# GCtoUSBv1_2.net
KiCad netlist of a schematic drawn in EAGLE
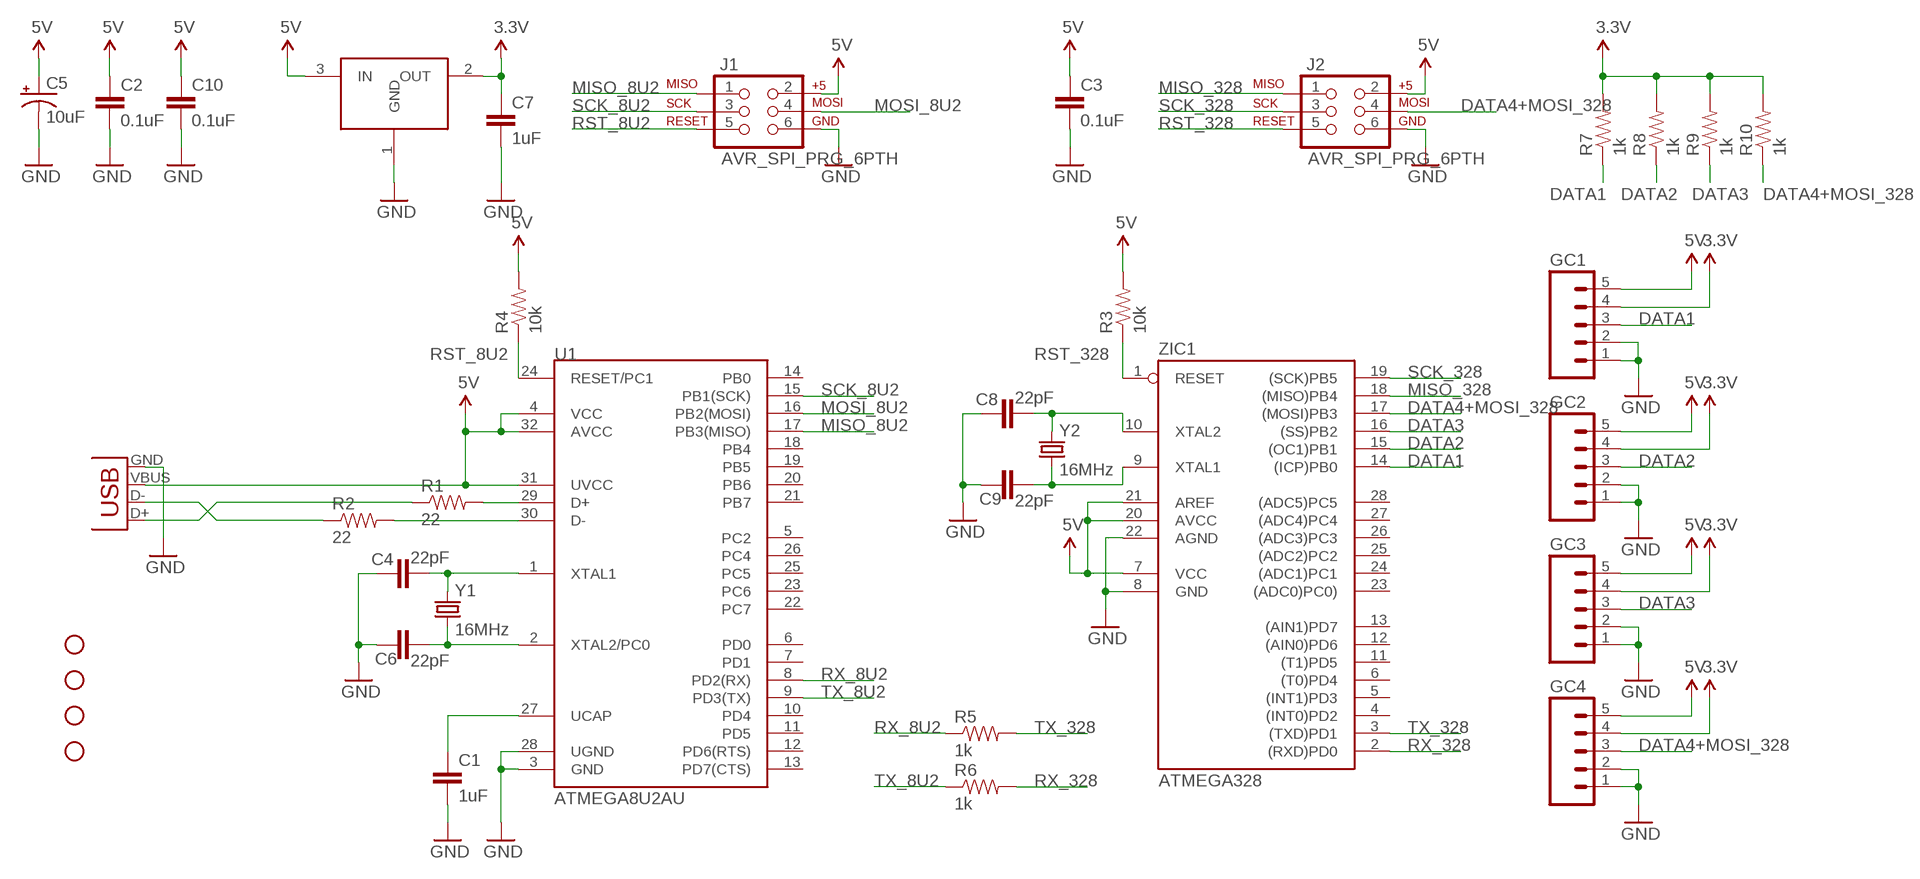
[diagram p0: schematic, sheet 1]

(export (version "E")
  (design (tool "Eeschema 10.0.6"))
  (components
    (comp (ref "C1")
      (value "1uF")
      (footprint "eagle-import:CAP-PTH-5MM")
      (libsource (lib "eagle-import") (part "CAPPTH1"))
    )
    (comp (ref "C2")
      (value "0.1uF")
      (footprint "eagle-import:CAP-PTH-SMALL")
      (libsource (lib "eagle-import") (part "CAPPTH"))
    )
    (comp (ref "C3")
      (value "0.1uF")
      (footprint "eagle-import:CAP-PTH-SMALL")
      (libsource (lib "eagle-import") (part "CAPPTH"))
    )
    (comp (ref "C4")
      (value "22pF")
      (footprint "eagle-import:CAP-PTH-SMALL")
      (libsource (lib "eagle-import") (part "CAPPTH"))
    )
    (comp (ref "C5")
      (value "10uF")
      (footprint "eagle-import:CPOL-RADIAL-10UF-25V")
      (libsource (lib "eagle-import") (part "CAP_POLPTH2"))
    )
    (comp (ref "C6")
      (value "22pF")
      (footprint "eagle-import:CAP-PTH-SMALL")
      (libsource (lib "eagle-import") (part "CAPPTH"))
    )
    (comp (ref "C7")
      (value "1uF")
      (footprint "eagle-import:CAP-PTH-5MM")
      (libsource (lib "eagle-import") (part "CAPPTH1"))
    )
    (comp (ref "C8")
      (value "22pF")
      (footprint "eagle-import:CAP-PTH-SMALL")
      (libsource (lib "eagle-import") (part "CAPPTH"))
    )
    (comp (ref "C9")
      (value "22pF")
      (footprint "eagle-import:CAP-PTH-SMALL")
      (libsource (lib "eagle-import") (part "CAPPTH"))
    )
    (comp (ref "C10")
      (value "0.1uF")
      (footprint "eagle-import:CAP-PTH-SMALL")
      (libsource (lib "eagle-import") (part "CAPPTH"))
    )
    (comp (ref "GC1")
      (value "M05PTH")
      (footprint "eagle-import:1X05")
      (libsource (lib "eagle-import") (part "M05PTH"))
    )
    (comp (ref "GC2")
      (value "M05PTH")
      (footprint "eagle-import:1X05")
      (libsource (lib "eagle-import") (part "M05PTH"))
    )
    (comp (ref "GC3")
      (value "M05PTH")
      (footprint "eagle-import:1X05")
      (libsource (lib "eagle-import") (part "M05PTH"))
    )
    (comp (ref "GC4")
      (value "M05PTH")
      (footprint "eagle-import:1X05")
      (libsource (lib "eagle-import") (part "M05PTH"))
    )
    (comp (ref "J1")
      (value "AVR_SPI_PRG_6PTH")
      (footprint "eagle-import:2X3")
      (libsource (lib "eagle-import") (part "AVR_SPI_PRG_6PTH"))
    )
    (comp (ref "J2")
      (value "AVR_SPI_PRG_6PTH")
      (footprint "eagle-import:2X3")
      (libsource (lib "eagle-import") (part "AVR_SPI_PRG_6PTH"))
    )
    (comp (ref "JP5")
      (value "STAND-OFF")
      (footprint "eagle-import:STAND-OFF")
      (libsource (lib "eagle-import") (part "STAND-OFF"))
    )
    (comp (ref "JP6")
      (value "STAND-OFF")
      (footprint "eagle-import:STAND-OFF")
      (libsource (lib "eagle-import") (part "STAND-OFF"))
    )
    (comp (ref "JP7")
      (value "STAND-OFF")
      (footprint "eagle-import:STAND-OFF")
      (libsource (lib "eagle-import") (part "STAND-OFF"))
    )
    (comp (ref "JP8")
      (value "STAND-OFF")
      (footprint "eagle-import:STAND-OFF")
      (libsource (lib "eagle-import") (part "STAND-OFF"))
    )
    (comp (ref "R1")
      (value "22")
      (footprint "eagle-import:AXIAL-0.4")
      (libsource (lib "eagle-import") (part "RESISTORPTH-1/4W"))
    )
    (comp (ref "R2")
      (value "22")
      (footprint "eagle-import:AXIAL-0.4")
      (libsource (lib "eagle-import") (part "RESISTORPTH-1/4W"))
    )
    (comp (ref "R3")
      (value "10k")
      (footprint "eagle-import:AXIAL-0.4")
      (libsource (lib "eagle-import") (part "RESISTORPTH-1/4W"))
    )
    (comp (ref "R4")
      (value "10k")
      (footprint "eagle-import:AXIAL-0.4")
      (libsource (lib "eagle-import") (part "RESISTORPTH-1/4W"))
    )
    (comp (ref "R5")
      (value "1k")
      (footprint "eagle-import:AXIAL-0.4")
      (libsource (lib "eagle-import") (part "RESISTORPTH-1/4W"))
    )
    (comp (ref "R6")
      (value "1k")
      (footprint "eagle-import:AXIAL-0.4")
      (libsource (lib "eagle-import") (part "RESISTORPTH-1/4W"))
    )
    (comp (ref "R7")
      (value "1k")
      (footprint "eagle-import:AXIAL-0.4")
      (libsource (lib "eagle-import") (part "RESISTORPTH-1/4W"))
    )
    (comp (ref "R8")
      (value "1k")
      (footprint "eagle-import:AXIAL-0.4")
      (libsource (lib "eagle-import") (part "RESISTORPTH-1/4W"))
    )
    (comp (ref "R9")
      (value "1k")
      (footprint "eagle-import:AXIAL-0.4")
      (libsource (lib "eagle-import") (part "RESISTORPTH-1/4W"))
    )
    (comp (ref "R10")
      (value "1k")
      (footprint "eagle-import:AXIAL-0.4")
      (libsource (lib "eagle-import") (part "RESISTORPTH-1/4W"))
    )
    (comp (ref "U$16")
      (value "TO220-LDOTO")
      (footprint "eagle-import:TO220V")
      (libsource (lib "eagle-import") (part "TO220-LDOTO"))
    )
    (comp (ref "U1")
      (value "ATMEGA8U2AU")
      (footprint "eagle-import:TQFP32-08")
      (libsource (lib "eagle-import") (part "ATMEGA8U2AU"))
    )
    (comp (ref "X1")
      (value "USB-MB-H")
      (footprint "eagle-import:USB-MB-H")
      (libsource (lib "eagle-import") (part "USB-MB-H"))
    )
    (comp (ref "Y1")
      (value "16MHz")
      (footprint "eagle-import:HC49US")
      (libsource (lib "eagle-import") (part "CRYSTALHC49US"))
    )
    (comp (ref "Y2")
      (value "16MHz")
      (footprint "eagle-import:HC49US")
      (libsource (lib "eagle-import") (part "CRYSTALHC49US"))
    )
    (comp (ref "ZIC1")
      (value "ATMEGA328")
      (footprint "eagle-import:DIL28-3")
      (libsource (lib "eagle-import") (part "AT90S4433P"))
    )
  )
  (nets
    (net (code "1") (name "/DATA1") (class "Default")
      (node (ref "GC1") (pin "3") (pinfunction "3_3") (pintype "passive"))
      (node (ref "R7") (pin "P$1") (pinfunction "1_P$1") (pintype "passive"))
      (node (ref "ZIC1") (pin "14") (pinfunction "(ICP)PB0_14") (pintype "bidirectional"))
    )
    (net (code "2") (name "/DATA2") (class "Default")
      (node (ref "GC2") (pin "3") (pinfunction "3_3") (pintype "passive"))
      (node (ref "R8") (pin "P$1") (pinfunction "1_P$1") (pintype "passive"))
      (node (ref "ZIC1") (pin "15") (pinfunction "(OC1)PB1_15") (pintype "bidirectional"))
    )
    (net (code "3") (name "/DATA3") (class "Default")
      (node (ref "GC3") (pin "3") (pinfunction "3_3") (pintype "passive"))
      (node (ref "R9") (pin "P$1") (pinfunction "1_P$1") (pintype "passive"))
      (node (ref "ZIC1") (pin "16") (pinfunction "(SS)PB2_16") (pintype "bidirectional"))
    )
    (net (code "4") (name "/DATA4+MOSI_328") (class "Default")
      (node (ref "GC4") (pin "3") (pinfunction "3_3") (pintype "passive"))
      (node (ref "J2") (pin "4") (pinfunction "4_4") (pintype "passive"))
      (node (ref "R10") (pin "P$1") (pinfunction "1_P$1") (pintype "passive"))
      (node (ref "ZIC1") (pin "17") (pinfunction "(MOSI)PB3_17") (pintype "bidirectional"))
    )
    (net (code "5") (name "/MISO_8U2") (class "Default")
      (node (ref "J1") (pin "1") (pinfunction "1_1") (pintype "passive"))
      (node (ref "U1") (pin "17") (pinfunction "PB3(MISO)_17") (pintype "bidirectional"))
    )
    (net (code "6") (name "/MISO_328") (class "Default")
      (node (ref "J2") (pin "1") (pinfunction "1_1") (pintype "passive"))
      (node (ref "ZIC1") (pin "18") (pinfunction "(MISO)PB4_18") (pintype "bidirectional"))
    )
    (net (code "7") (name "/MOSI_8U2") (class "Default")
      (node (ref "J1") (pin "4") (pinfunction "4_4") (pintype "passive"))
      (node (ref "U1") (pin "16") (pinfunction "PB2(MOSI)_16") (pintype "bidirectional"))
    )
    (net (code "8") (name "/RST_8U2") (class "Default")
      (node (ref "J1") (pin "5") (pinfunction "5_5") (pintype "passive"))
      (node (ref "R4") (pin "P$1") (pinfunction "1_P$1") (pintype "passive"))
      (node (ref "U1") (pin "24") (pinfunction "RESET/PC1_24") (pintype "bidirectional"))
    )
    (net (code "9") (name "/RST_328") (class "Default")
      (node (ref "J2") (pin "5") (pinfunction "5_5") (pintype "passive"))
      (node (ref "R3") (pin "P$1") (pinfunction "1_P$1") (pintype "passive"))
      (node (ref "ZIC1") (pin "1") (pinfunction "RESET_1") (pintype "input"))
    )
    (net (code "10") (name "/RX_8U2") (class "Default")
      (node (ref "R5") (pin "P$1") (pinfunction "1_P$1") (pintype "passive"))
      (node (ref "U1") (pin "8") (pinfunction "PD2(RX)_8") (pintype "bidirectional"))
    )
    (net (code "11") (name "/RX_328") (class "Default")
      (node (ref "R6") (pin "P$2") (pinfunction "2_P$2") (pintype "passive"))
      (node (ref "ZIC1") (pin "2") (pinfunction "(RXD)PD0_2") (pintype "bidirectional"))
    )
    (net (code "12") (name "/SCK_8U2") (class "Default")
      (node (ref "J1") (pin "3") (pinfunction "3_3") (pintype "passive"))
      (node (ref "U1") (pin "15") (pinfunction "PB1(SCK)_15") (pintype "bidirectional"))
    )
    (net (code "13") (name "/SCK_328") (class "Default")
      (node (ref "J2") (pin "3") (pinfunction "3_3") (pintype "passive"))
      (node (ref "ZIC1") (pin "19") (pinfunction "(SCK)PB5_19") (pintype "bidirectional"))
    )
    (net (code "14") (name "/TX_8U2") (class "Default")
      (node (ref "R6") (pin "P$1") (pinfunction "1_P$1") (pintype "passive"))
      (node (ref "U1") (pin "9") (pinfunction "PD3(TX)_9") (pintype "bidirectional"))
    )
    (net (code "15") (name "/TX_328") (class "Default")
      (node (ref "R5") (pin "P$2") (pinfunction "2_P$2") (pintype "passive"))
      (node (ref "ZIC1") (pin "3") (pinfunction "(TXD)PD1_3") (pintype "bidirectional"))
    )
    (net (code "16") (name "3.3V") (class "Default")
      (node (ref "C7") (pin "1") (pinfunction "1_1") (pintype "passive"))
      (node (ref "GC1") (pin "4") (pinfunction "4_4") (pintype "passive"))
      (node (ref "GC2") (pin "4") (pinfunction "4_4") (pintype "passive"))
      (node (ref "GC3") (pin "4") (pinfunction "4_4") (pintype "passive"))
      (node (ref "GC4") (pin "4") (pinfunction "4_4") (pintype "passive"))
      (node (ref "R10") (pin "P$2") (pinfunction "2_P$2") (pintype "passive"))
      (node (ref "R7") (pin "P$2") (pinfunction "2_P$2") (pintype "passive"))
      (node (ref "R8") (pin "P$2") (pinfunction "2_P$2") (pintype "passive"))
      (node (ref "R9") (pin "P$2") (pinfunction "2_P$2") (pintype "passive"))
      (node (ref "U$16") (pin "2") (pinfunction "OUT_2") (pintype "bidirectional"))
    )
    (net (code "17") (name "5V") (class "Default")
      (node (ref "C10") (pin "1") (pinfunction "1_1") (pintype "passive"))
      (node (ref "C2") (pin "1") (pinfunction "1_1") (pintype "passive"))
      (node (ref "C3") (pin "1") (pinfunction "1_1") (pintype "passive"))
      (node (ref "C5") (pin "1") (pinfunction "+_1") (pintype "passive"))
      (node (ref "GC1") (pin "5") (pinfunction "5_5") (pintype "passive"))
      (node (ref "GC2") (pin "5") (pinfunction "5_5") (pintype "passive"))
      (node (ref "GC3") (pin "5") (pinfunction "5_5") (pintype "passive"))
      (node (ref "GC4") (pin "5") (pinfunction "5_5") (pintype "passive"))
      (node (ref "J1") (pin "2") (pinfunction "2_2") (pintype "passive"))
      (node (ref "J2") (pin "2") (pinfunction "2_2") (pintype "passive"))
      (node (ref "R3") (pin "P$2") (pinfunction "2_P$2") (pintype "passive"))
      (node (ref "R4") (pin "P$2") (pinfunction "2_P$2") (pintype "passive"))
      (node (ref "U$16") (pin "3") (pinfunction "IN_3") (pintype "bidirectional"))
      (node (ref "U1") (pin "31") (pinfunction "UVCC_31") (pintype "bidirectional"))
      (node (ref "U1") (pin "32") (pinfunction "AVCC_32") (pintype "bidirectional"))
      (node (ref "U1") (pin "4") (pinfunction "VCC_4") (pintype "bidirectional"))
      (node (ref "X1") (pin "VBUS") (pinfunction "VBUS_VBUS") (pintype "bidirectional"))
      (node (ref "ZIC1") (pin "20") (pinfunction "AVCC_20") (pintype "power_in"))
      (node (ref "ZIC1") (pin "21") (pinfunction "AREF_21") (pintype "passive"))
      (node (ref "ZIC1") (pin "7") (pinfunction "VCC_7") (pintype "power_in"))
    )
    (net (code "18") (name "GND") (class "Default")
      (node (ref "C1") (pin "2") (pinfunction "2_2") (pintype "passive"))
      (node (ref "C10") (pin "2") (pinfunction "2_2") (pintype "passive"))
      (node (ref "C2") (pin "2") (pinfunction "2_2") (pintype "passive"))
      (node (ref "C3") (pin "2") (pinfunction "2_2") (pintype "passive"))
      (node (ref "C4") (pin "2") (pinfunction "2_2") (pintype "passive"))
      (node (ref "C5") (pin "2") (pinfunction "-_2") (pintype "passive"))
      (node (ref "C6") (pin "2") (pinfunction "2_2") (pintype "passive"))
      (node (ref "C7") (pin "2") (pinfunction "2_2") (pintype "passive"))
      (node (ref "C8") (pin "2") (pinfunction "2_2") (pintype "passive"))
      (node (ref "C9") (pin "2") (pinfunction "2_2") (pintype "passive"))
      (node (ref "GC1") (pin "1") (pinfunction "1_1") (pintype "passive"))
      (node (ref "GC1") (pin "2") (pinfunction "2_2") (pintype "passive"))
      (node (ref "GC2") (pin "1") (pinfunction "1_1") (pintype "passive"))
      (node (ref "GC2") (pin "2") (pinfunction "2_2") (pintype "passive"))
      (node (ref "GC3") (pin "1") (pinfunction "1_1") (pintype "passive"))
      (node (ref "GC3") (pin "2") (pinfunction "2_2") (pintype "passive"))
      (node (ref "GC4") (pin "1") (pinfunction "1_1") (pintype "passive"))
      (node (ref "GC4") (pin "2") (pinfunction "2_2") (pintype "passive"))
      (node (ref "J1") (pin "6") (pinfunction "6_6") (pintype "passive"))
      (node (ref "J2") (pin "6") (pinfunction "6_6") (pintype "passive"))
      (node (ref "U$16") (pin "1") (pinfunction "GND_1") (pintype "bidirectional"))
      (node (ref "U1") (pin "28") (pinfunction "UGND_28") (pintype "bidirectional"))
      (node (ref "U1") (pin "3") (pinfunction "GND_3") (pintype "bidirectional"))
      (node (ref "X1") (pin "GND") (pinfunction "GND_GND") (pintype "bidirectional"))
      (node (ref "ZIC1") (pin "22") (pinfunction "AGND_22") (pintype "power_in"))
      (node (ref "ZIC1") (pin "8") (pinfunction "GND_8") (pintype "power_in"))
    )
    (net (code "19") (name "Net-(R1-1)") (class "Default")
      (node (ref "R1") (pin "P$1") (pinfunction "1_P$1") (pintype "passive"))
      (node (ref "X1") (pin "D+") (pinfunction "D+_D+") (pintype "bidirectional"))
    )
    (net (code "20") (name "Net-(R1-2)") (class "Default")
      (node (ref "R1") (pin "P$2") (pinfunction "2_P$2") (pintype "passive"))
      (node (ref "U1") (pin "29") (pinfunction "D+_29") (pintype "bidirectional"))
    )
    (net (code "21") (name "Net-(R2-1)") (class "Default")
      (node (ref "R2") (pin "P$1") (pinfunction "1_P$1") (pintype "passive"))
      (node (ref "X1") (pin "D-") (pinfunction "D-_D-") (pintype "bidirectional"))
    )
    (net (code "22") (name "Net-(R2-2)") (class "Default")
      (node (ref "R2") (pin "P$2") (pinfunction "2_P$2") (pintype "passive"))
      (node (ref "U1") (pin "30") (pinfunction "D-_30") (pintype "bidirectional"))
    )
    (net (code "23") (name "Net-(U1-UCAP)") (class "Default")
      (node (ref "C1") (pin "1") (pinfunction "1_1") (pintype "passive"))
      (node (ref "U1") (pin "27") (pinfunction "UCAP_27") (pintype "bidirectional"))
    )
    (net (code "24") (name "Net-(U1-XTAL1)") (class "Default")
      (node (ref "C4") (pin "1") (pinfunction "1_1") (pintype "passive"))
      (node (ref "U1") (pin "1") (pinfunction "XTAL1_1") (pintype "bidirectional"))
      (node (ref "Y1") (pin "2") (pinfunction "2_2") (pintype "passive"))
    )
    (net (code "25") (name "Net-(U1-XTAL2{slash}PC0)") (class "Default")
      (node (ref "C6") (pin "1") (pinfunction "1_1") (pintype "passive"))
      (node (ref "U1") (pin "2") (pinfunction "XTAL2/PC0_2") (pintype "bidirectional"))
      (node (ref "Y1") (pin "1") (pinfunction "1_1") (pintype "passive"))
    )
    (net (code "26") (name "Net-(ZIC1-XTAL1)") (class "Default")
      (node (ref "C9") (pin "1") (pinfunction "1_1") (pintype "passive"))
      (node (ref "Y2") (pin "1") (pinfunction "1_1") (pintype "passive"))
      (node (ref "ZIC1") (pin "9") (pinfunction "XTAL1_9") (pintype "bidirectional"))
    )
    (net (code "27") (name "Net-(ZIC1-XTAL2)") (class "Default")
      (node (ref "C8") (pin "1") (pinfunction "1_1") (pintype "passive"))
      (node (ref "Y2") (pin "2") (pinfunction "2_2") (pintype "passive"))
      (node (ref "ZIC1") (pin "10") (pinfunction "XTAL2_10") (pintype "bidirectional"))
    )
    (net (code "28") (name "unconnected-(U1-PB0-Pad14)") (class "Default")
      (node (ref "U1") (pin "14") (pinfunction "PB0_14") (pintype "bidirectional"))
    )
    (net (code "29") (name "unconnected-(U1-PB4-Pad18)") (class "Default")
      (node (ref "U1") (pin "18") (pinfunction "PB4_18") (pintype "bidirectional"))
    )
    (net (code "30") (name "unconnected-(U1-PB5-Pad19)") (class "Default")
      (node (ref "U1") (pin "19") (pinfunction "PB5_19") (pintype "bidirectional"))
    )
    (net (code "31") (name "unconnected-(U1-PB6-Pad20)") (class "Default")
      (node (ref "U1") (pin "20") (pinfunction "PB6_20") (pintype "bidirectional"))
    )
    (net (code "32") (name "unconnected-(U1-PB7-Pad21)") (class "Default")
      (node (ref "U1") (pin "21") (pinfunction "PB7_21") (pintype "bidirectional"))
    )
    (net (code "33") (name "unconnected-(U1-PC2-Pad5)") (class "Default")
      (node (ref "U1") (pin "5") (pinfunction "PC2_5") (pintype "bidirectional"))
    )
    (net (code "34") (name "unconnected-(U1-PC4-Pad26)") (class "Default")
      (node (ref "U1") (pin "26") (pinfunction "PC4_26") (pintype "bidirectional"))
    )
    (net (code "35") (name "unconnected-(U1-PC5-Pad25)") (class "Default")
      (node (ref "U1") (pin "25") (pinfunction "PC5_25") (pintype "bidirectional"))
    )
    (net (code "36") (name "unconnected-(U1-PC6-Pad23)") (class "Default")
      (node (ref "U1") (pin "23") (pinfunction "PC6_23") (pintype "bidirectional"))
    )
    (net (code "37") (name "unconnected-(U1-PC7-Pad22)") (class "Default")
      (node (ref "U1") (pin "22") (pinfunction "PC7_22") (pintype "bidirectional"))
    )
    (net (code "38") (name "unconnected-(U1-PD0-Pad6)") (class "Default")
      (node (ref "U1") (pin "6") (pinfunction "PD0_6") (pintype "bidirectional"))
    )
    (net (code "39") (name "unconnected-(U1-PD1-Pad7)") (class "Default")
      (node (ref "U1") (pin "7") (pinfunction "PD1_7") (pintype "bidirectional"))
    )
    (net (code "40") (name "unconnected-(U1-PD4-Pad10)") (class "Default")
      (node (ref "U1") (pin "10") (pinfunction "PD4_10") (pintype "bidirectional"))
    )
    (net (code "41") (name "unconnected-(U1-PD5-Pad11)") (class "Default")
      (node (ref "U1") (pin "11") (pinfunction "PD5_11") (pintype "bidirectional"))
    )
    (net (code "42") (name "unconnected-(U1-PD6(RTS)-Pad12)") (class "Default")
      (node (ref "U1") (pin "12") (pinfunction "PD6(RTS)_12") (pintype "bidirectional"))
    )
    (net (code "43") (name "unconnected-(U1-PD7(CTS)-Pad13)") (class "Default")
      (node (ref "U1") (pin "13") (pinfunction "PD7(CTS)_13") (pintype "bidirectional"))
    )
    (net (code "44") (name "unconnected-(ZIC1-(ADC0)PC0)-Pad23)") (class "Default")
      (node (ref "ZIC1") (pin "23") (pinfunction "(ADC0)PC0)_23") (pintype "bidirectional"))
    )
    (net (code "45") (name "unconnected-(ZIC1-(ADC1)PC1-Pad24)") (class "Default")
      (node (ref "ZIC1") (pin "24") (pinfunction "(ADC1)PC1_24") (pintype "bidirectional"))
    )
    (net (code "46") (name "unconnected-(ZIC1-(ADC2)PC2-Pad25)") (class "Default")
      (node (ref "ZIC1") (pin "25") (pinfunction "(ADC2)PC2_25") (pintype "bidirectional"))
    )
    (net (code "47") (name "unconnected-(ZIC1-(ADC3)PC3-Pad26)") (class "Default")
      (node (ref "ZIC1") (pin "26") (pinfunction "(ADC3)PC3_26") (pintype "bidirectional"))
    )
    (net (code "48") (name "unconnected-(ZIC1-(ADC4)PC4-Pad27)") (class "Default")
      (node (ref "ZIC1") (pin "27") (pinfunction "(ADC4)PC4_27") (pintype "bidirectional"))
    )
    (net (code "49") (name "unconnected-(ZIC1-(ADC5)PC5-Pad28)") (class "Default")
      (node (ref "ZIC1") (pin "28") (pinfunction "(ADC5)PC5_28") (pintype "bidirectional"))
    )
    (net (code "50") (name "unconnected-(ZIC1-(AIN0)PD6-Pad12)") (class "Default")
      (node (ref "ZIC1") (pin "12") (pinfunction "(AIN0)PD6_12") (pintype "bidirectional"))
    )
    (net (code "51") (name "unconnected-(ZIC1-(AIN1)PD7-Pad13)") (class "Default")
      (node (ref "ZIC1") (pin "13") (pinfunction "(AIN1)PD7_13") (pintype "bidirectional"))
    )
    (net (code "52") (name "unconnected-(ZIC1-(INT0)PD2-Pad4)") (class "Default")
      (node (ref "ZIC1") (pin "4") (pinfunction "(INT0)PD2_4") (pintype "bidirectional"))
    )
    (net (code "53") (name "unconnected-(ZIC1-(INT1)PD3-Pad5)") (class "Default")
      (node (ref "ZIC1") (pin "5") (pinfunction "(INT1)PD3_5") (pintype "bidirectional"))
    )
    (net (code "54") (name "unconnected-(ZIC1-(T0)PD4-Pad6)") (class "Default")
      (node (ref "ZIC1") (pin "6") (pinfunction "(T0)PD4_6") (pintype "bidirectional"))
    )
    (net (code "55") (name "unconnected-(ZIC1-(T1)PD5-Pad11)") (class "Default")
      (node (ref "ZIC1") (pin "11") (pinfunction "(T1)PD5_11") (pintype "bidirectional"))
    )
  )
)
